# Display.net
KiCad netlist of a schematic drawn in Altium Designer
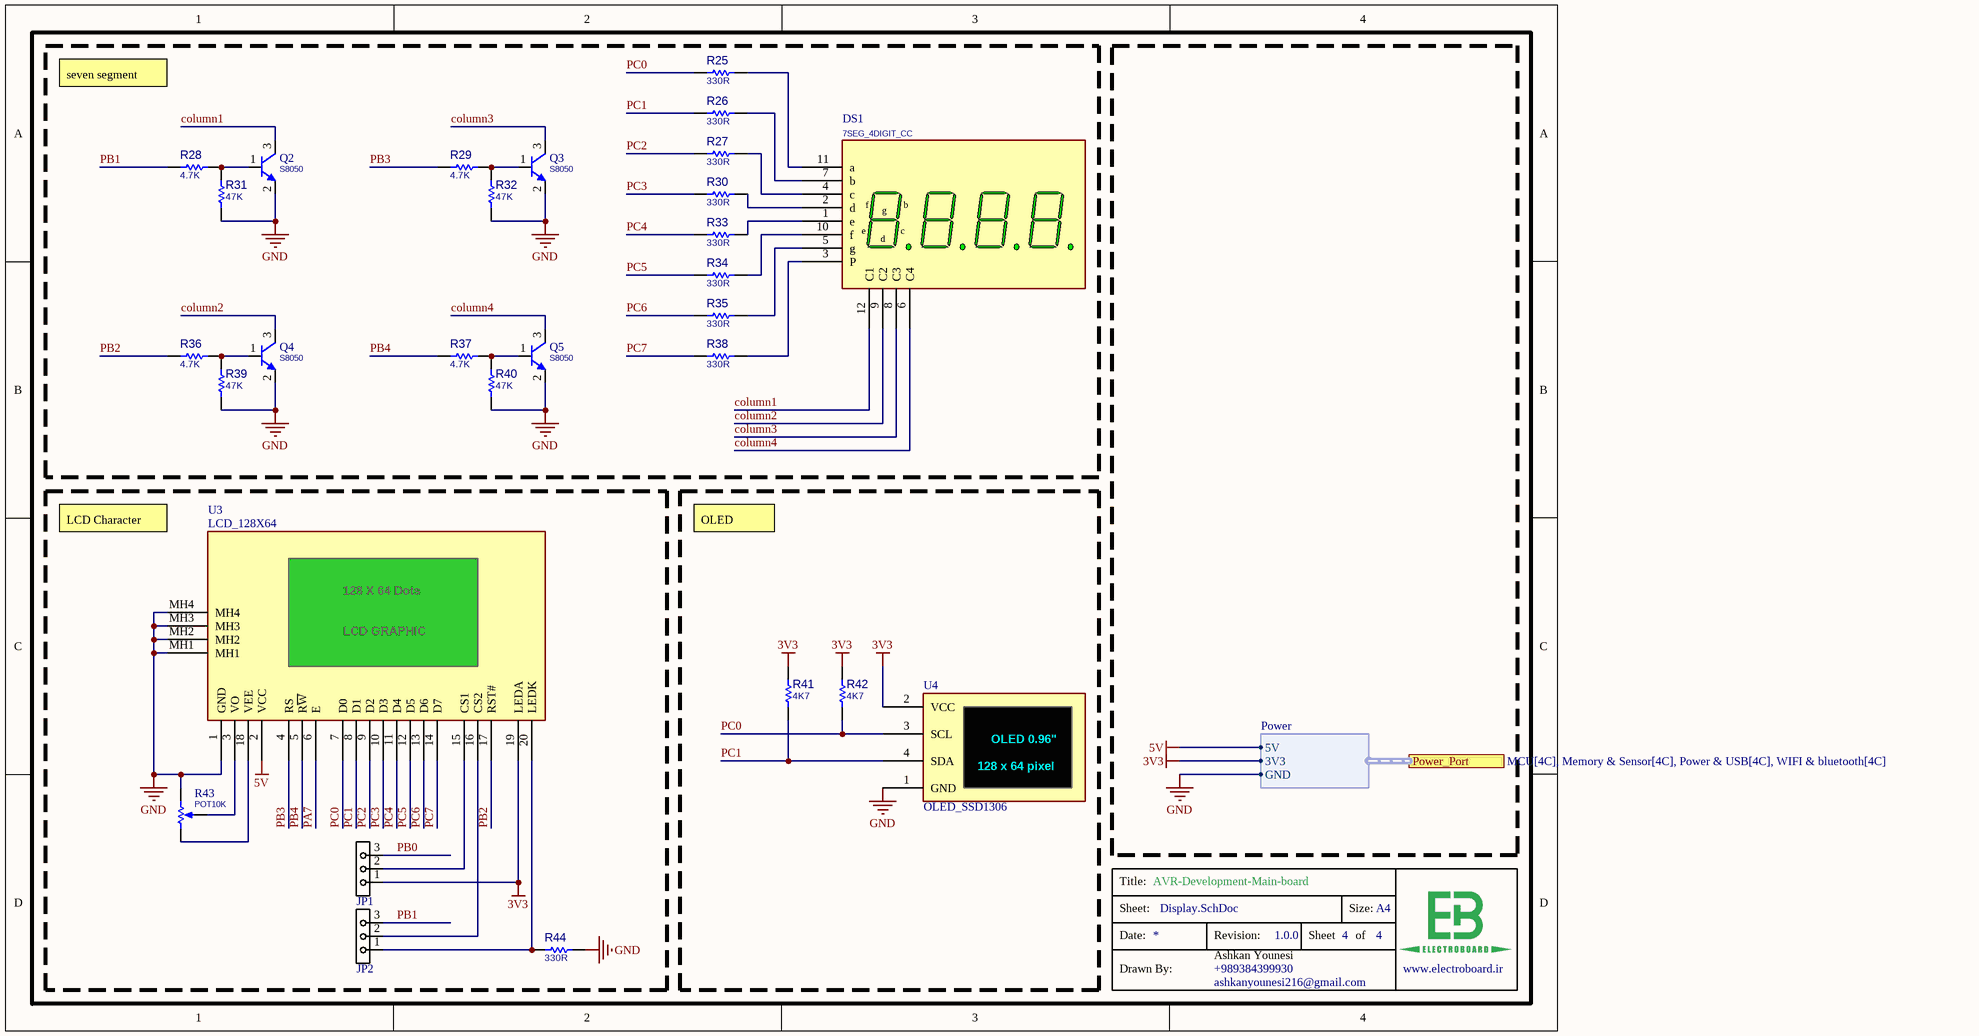
[diagram p0: Display.SchDoc]

(export (version "E")
  (design (tool "Eeschema 10.0.6"))
  (components
    (comp (ref "DS1")
      (value "7SEG_4DIGIT_CC")
      (footprint "7SEGX4_12")
      (description "7SEGMENT, 4DIGIT, common cathode 5641")
      (fields (field (name "MANF_P#") "DPY-4CK"))
      (libsource (lib "7seg(LED)") (part "7SEG_4DIGIT_CC"))
    )
    (comp (ref "JP1")
      (value "JMPHDR3PIN")
      (footprint "JP_3")
      (description "JUMPER, HEADER 3PIN")
      (fields (field (name "MANF") "MANF") (field (name "MANF_P#") "MANF_P#"))
      (libsource (lib "test-tp_jumper") (part "JUMPER_HDR_3P"))
    )
    (comp (ref "JP2")
      (value "JMPHDR3PIN")
      (footprint "JP_3")
      (description "JUMPER, HEADER 3PIN")
      (fields (field (name "MANF") "MANF") (field (name "MANF_P#") "MANF_P#"))
      (libsource (lib "test-tp_jumper") (part "JUMPER_HDR_3P"))
    )
    (comp (ref "Q2")
      (value "S8050")
      (footprint "SOT23_3")
      (description "BJT, NPN, 25v, 0.5A, SMD, SOT23")
      (libsource (lib "transistor_bjt") (part "NPN_S8050_SOT23"))
    )
    (comp (ref "Q3")
      (value "S8050")
      (footprint "SOT23_3")
      (description "BJT, NPN, 25v, 0.5A, SMD, SOT23")
      (libsource (lib "transistor_bjt") (part "NPN_S8050_SOT23"))
    )
    (comp (ref "Q4")
      (value "S8050")
      (footprint "SOT23_3")
      (description "BJT, NPN, 25v, 0.5A, SMD, SOT23")
      (libsource (lib "transistor_bjt") (part "NPN_S8050_SOT23"))
    )
    (comp (ref "Q5")
      (value "S8050")
      (footprint "SOT23_3")
      (description "BJT, NPN, 25v, 0.5A, SMD, SOT23")
      (libsource (lib "transistor_bjt") (part "NPN_S8050_SOT23"))
    )
    (comp (ref "R25")
      (value "330R")
      (footprint "R0805")
      (description "RESISTOR, SMD")
      (libsource (lib "passive_smd") (part "RES_SMD_0805"))
    )
    (comp (ref "R26")
      (value "330R")
      (footprint "R0805")
      (description "RESISTOR, SMD")
      (libsource (lib "passive_smd") (part "RES_SMD_0805"))
    )
    (comp (ref "R27")
      (value "330R")
      (footprint "R0805")
      (description "RESISTOR, SMD")
      (libsource (lib "passive_smd") (part "RES_SMD_0805"))
    )
    (comp (ref "R28")
      (value "4.7K")
      (footprint "R0805")
      (description "RESISTOR, SMD")
      (libsource (lib "passive_smd") (part "RES_SMD_0805"))
    )
    (comp (ref "R29")
      (value "4.7K")
      (footprint "R0805")
      (description "RESISTOR, SMD")
      (libsource (lib "passive_smd") (part "RES_SMD_0805"))
    )
    (comp (ref "R30")
      (value "330R")
      (footprint "R0805")
      (description "RESISTOR, SMD")
      (libsource (lib "passive_smd") (part "RES_SMD_0805"))
    )
    (comp (ref "R31")
      (value "47K")
      (footprint "R0805")
      (description "RESISTOR, SMD")
      (libsource (lib "passive_smd") (part "RES_SMD_0805"))
    )
    (comp (ref "R32")
      (value "47K")
      (footprint "R0805")
      (description "RESISTOR, SMD")
      (libsource (lib "passive_smd") (part "RES_SMD_0805"))
    )
    (comp (ref "R33")
      (value "330R")
      (footprint "R0805")
      (description "RESISTOR, SMD")
      (libsource (lib "passive_smd") (part "RES_SMD_0805"))
    )
    (comp (ref "R34")
      (value "330R")
      (footprint "R0805")
      (description "RESISTOR, SMD")
      (libsource (lib "passive_smd") (part "RES_SMD_0805"))
    )
    (comp (ref "R35")
      (value "330R")
      (footprint "R0805")
      (description "RESISTOR, SMD")
      (libsource (lib "passive_smd") (part "RES_SMD_0805"))
    )
    (comp (ref "R36")
      (value "4.7K")
      (footprint "R0805")
      (description "RESISTOR, SMD")
      (libsource (lib "passive_smd") (part "RES_SMD_0805"))
    )
    (comp (ref "R37")
      (value "4.7K")
      (footprint "R0805")
      (description "RESISTOR, SMD")
      (libsource (lib "passive_smd") (part "RES_SMD_0805"))
    )
    (comp (ref "R38")
      (value "330R")
      (footprint "R0805")
      (description "RESISTOR, SMD")
      (libsource (lib "passive_smd") (part "RES_SMD_0805"))
    )
    (comp (ref "R39")
      (value "47K")
      (footprint "R0805")
      (description "RESISTOR, SMD")
      (libsource (lib "passive_smd") (part "RES_SMD_0805"))
    )
    (comp (ref "R40")
      (value "47K")
      (footprint "R0805")
      (description "RESISTOR, SMD")
      (libsource (lib "passive_smd") (part "RES_SMD_0805"))
    )
    (comp (ref "R41")
      (value "4K7")
      (footprint "R0805")
      (description "RESISTOR, SMD")
      (libsource (lib "passive_smd") (part "RES_SMD_0805"))
    )
    (comp (ref "R42")
      (value "4K7")
      (footprint "R0805")
      (description "RESISTOR, SMD")
      (libsource (lib "passive_smd") (part "RES_SMD_0805"))
    )
    (comp (ref "R43")
      (value "POT10K")
      (footprint "POT_3296W")
      (description "RESISTOR, THD, Potentiometer Multiturn, most Popular")
      (libsource (lib "resistor_pot_trimmer") (part "RES_THD_POT_MULTITURN"))
    )
    (comp (ref "R44")
      (value "330R")
      (footprint "R0805")
      (description "RESISTOR, SMD")
      (libsource (lib "passive_smd") (part "RES_SMD_0805"))
    )
    (comp (ref "U3")
      (value "LCD_128X64")
      (footprint "LCDG_128X64_GRN")
      (description "LCD Graphic Disp, 128X64, with KS108 Controller")
      (fields (field (name "MANF") "Winstar") (field (name "MANF_P#") "TS12864A-2, WG12864A-1"))
      (libsource (lib "lcd") (part "LCDG_128X64_GRN"))
    )
    (comp (ref "U4")
      (value "OLED_SSD1306")
      (footprint "OLED_SSD1306_64_I2C")
      (description "OLED, SSD1306, 0.96\", 128X64, BREAKOUT I2C")
      (fields (field (name "MANF_P#") "OLED_SSD1306_I2C"))
      (libsource (lib "oled") (part "OLED_SSD1306_64_I2C"))
    )
  )
  (nets
    (net (code "2") (name "/PA7") (class "Default")
      (node (ref "U3") (pin "6") (pinfunction "E_6") (pintype "passive"))
    )
    (net (code "3") (name "/PB0") (class "Default")
      (node (ref "JP1") (pin "3") (pinfunction "3_3") (pintype "passive"))
    )
    (net (code "4") (name "/PB1") (class "Default")
      (node (ref "JP2") (pin "3") (pinfunction "3_3") (pintype "passive"))
      (node (ref "R28") (pin "1") (pinfunction "1_1") (pintype "passive"))
    )
    (net (code "5") (name "/PB2") (class "Default")
      (node (ref "R36") (pin "1") (pinfunction "1_1") (pintype "passive"))
      (node (ref "U3") (pin "17") (pinfunction "RST#_17") (pintype "passive"))
    )
    (net (code "6") (name "/PB3") (class "Default")
      (node (ref "R29") (pin "1") (pinfunction "1_1") (pintype "passive"))
      (node (ref "U3") (pin "4") (pinfunction "RS_4") (pintype "passive"))
    )
    (net (code "7") (name "/PB4") (class "Default")
      (node (ref "R37") (pin "1") (pinfunction "1_1") (pintype "passive"))
      (node (ref "U3") (pin "5") (pinfunction "R~{W}_5") (pintype "passive"))
    )
    (net (code "8") (name "/PC0") (class "Default")
      (node (ref "R25") (pin "1") (pinfunction "1_1") (pintype "passive"))
      (node (ref "R42") (pin "2") (pinfunction "2_2") (pintype "passive"))
      (node (ref "U3") (pin "7") (pinfunction "D0_7") (pintype "passive"))
      (node (ref "U4") (pin "3") (pinfunction "SCL_3") (pintype "passive"))
    )
    (net (code "9") (name "/PC1") (class "Default")
      (node (ref "R26") (pin "1") (pinfunction "1_1") (pintype "passive"))
      (node (ref "R41") (pin "2") (pinfunction "2_2") (pintype "passive"))
      (node (ref "U3") (pin "8") (pinfunction "D1_8") (pintype "passive"))
      (node (ref "U4") (pin "4") (pinfunction "SDA_4") (pintype "passive"))
    )
    (net (code "10") (name "/PC2") (class "Default")
      (node (ref "R27") (pin "1") (pinfunction "1_1") (pintype "passive"))
      (node (ref "U3") (pin "9") (pinfunction "D2_9") (pintype "passive"))
    )
    (net (code "11") (name "/PC3") (class "Default")
      (node (ref "R30") (pin "1") (pinfunction "1_1") (pintype "passive"))
      (node (ref "U3") (pin "10") (pinfunction "D3_10") (pintype "passive"))
    )
    (net (code "12") (name "/PC4") (class "Default")
      (node (ref "R33") (pin "1") (pinfunction "1_1") (pintype "passive"))
      (node (ref "U3") (pin "11") (pinfunction "D4_11") (pintype "passive"))
    )
    (net (code "13") (name "/PC5") (class "Default")
      (node (ref "R34") (pin "1") (pinfunction "1_1") (pintype "passive"))
      (node (ref "U3") (pin "12") (pinfunction "D5_12") (pintype "passive"))
    )
    (net (code "14") (name "/PC6") (class "Default")
      (node (ref "R35") (pin "1") (pinfunction "1_1") (pintype "passive"))
      (node (ref "U3") (pin "13") (pinfunction "D6_13") (pintype "passive"))
    )
    (net (code "15") (name "/PC7") (class "Default")
      (node (ref "R38") (pin "1") (pinfunction "1_1") (pintype "passive"))
      (node (ref "U3") (pin "14") (pinfunction "D7_14") (pintype "passive"))
    )
    (net (code "16") (name "/column1") (class "Default")
      (node (ref "DS1") (pin "12") (pinfunction "C1_12") (pintype "passive"))
      (node (ref "Q2") (pin "3") (pinfunction "C_3") (pintype "passive"))
    )
    (net (code "17") (name "/column2") (class "Default")
      (node (ref "DS1") (pin "9") (pinfunction "C2_9") (pintype "passive"))
      (node (ref "Q4") (pin "3") (pinfunction "C_3") (pintype "passive"))
    )
    (net (code "18") (name "/column3") (class "Default")
      (node (ref "DS1") (pin "8") (pinfunction "C3_8") (pintype "passive"))
      (node (ref "Q3") (pin "3") (pinfunction "C_3") (pintype "passive"))
    )
    (net (code "19") (name "/column4") (class "Default")
      (node (ref "DS1") (pin "6") (pinfunction "C4_6") (pintype "passive"))
      (node (ref "Q5") (pin "3") (pinfunction "C_3") (pintype "passive"))
    )
    (net (code "21") (name "3V3") (class "Default")
      (node (ref "JP1") (pin "1") (pinfunction "1_1") (pintype "passive"))
      (node (ref "R41") (pin "1") (pinfunction "1_1") (pintype "passive"))
      (node (ref "R42") (pin "1") (pinfunction "1_1") (pintype "passive"))
      (node (ref "U3") (pin "19") (pinfunction "LEDA_19") (pintype "passive"))
      (node (ref "U4") (pin "2") (pinfunction "VCC_2") (pintype "passive"))
    )
    (net (code "22") (name "5V") (class "Default")
      (node (ref "U3") (pin "2") (pinfunction "VCC_2") (pintype "passive"))
    )
    (net (code "23") (name "GND") (class "Default")
      (node (ref "Q2") (pin "2") (pinfunction "E_2") (pintype "passive"))
      (node (ref "Q3") (pin "2") (pinfunction "E_2") (pintype "passive"))
      (node (ref "Q4") (pin "2") (pinfunction "E_2") (pintype "passive"))
      (node (ref "Q5") (pin "2") (pinfunction "E_2") (pintype "passive"))
      (node (ref "R31") (pin "1") (pinfunction "1_1") (pintype "passive"))
      (node (ref "R32") (pin "1") (pinfunction "1_1") (pintype "passive"))
      (node (ref "R39") (pin "1") (pinfunction "1_1") (pintype "passive"))
      (node (ref "R40") (pin "1") (pinfunction "1_1") (pintype "passive"))
      (node (ref "R43") (pin "3") (pinfunction "BOT_3") (pintype "passive"))
      (node (ref "R44") (pin "1") (pinfunction "1_1") (pintype "passive"))
      (node (ref "U3") (pin "1") (pinfunction "GND_1") (pintype "passive"))
      (node (ref "U3") (pin "MH1") (pinfunction "MH1_MH1") (pintype "passive"))
      (node (ref "U3") (pin "MH2") (pinfunction "MH2_MH2") (pintype "passive"))
      (node (ref "U3") (pin "MH3") (pinfunction "MH3_MH3") (pintype "passive"))
      (node (ref "U3") (pin "MH4") (pinfunction "MH4_MH4") (pintype "passive"))
      (node (ref "U4") (pin "1") (pinfunction "GND_1") (pintype "passive"))
    )
    (net (code "24") (name "Net-(DS1-P)") (class "Default")
      (node (ref "DS1") (pin "3") (pinfunction "P_3") (pintype "passive"))
      (node (ref "R38") (pin "2") (pinfunction "2_2") (pintype "passive"))
    )
    (net (code "25") (name "Net-(DS1-a)") (class "Default")
      (node (ref "DS1") (pin "11") (pinfunction "a_11") (pintype "passive"))
      (node (ref "R25") (pin "2") (pinfunction "2_2") (pintype "passive"))
    )
    (net (code "26") (name "Net-(DS1-b)") (class "Default")
      (node (ref "DS1") (pin "7") (pinfunction "b_7") (pintype "passive"))
      (node (ref "R26") (pin "2") (pinfunction "2_2") (pintype "passive"))
    )
    (net (code "27") (name "Net-(DS1-c)") (class "Default")
      (node (ref "DS1") (pin "4") (pinfunction "c_4") (pintype "passive"))
      (node (ref "R27") (pin "2") (pinfunction "2_2") (pintype "passive"))
    )
    (net (code "28") (name "Net-(DS1-d)") (class "Default")
      (node (ref "DS1") (pin "2") (pinfunction "d_2") (pintype "passive"))
      (node (ref "R30") (pin "2") (pinfunction "2_2") (pintype "passive"))
    )
    (net (code "29") (name "Net-(DS1-e)") (class "Default")
      (node (ref "DS1") (pin "1") (pinfunction "e_1") (pintype "passive"))
      (node (ref "R33") (pin "2") (pinfunction "2_2") (pintype "passive"))
    )
    (net (code "30") (name "Net-(DS1-f)") (class "Default")
      (node (ref "DS1") (pin "10") (pinfunction "f_10") (pintype "passive"))
      (node (ref "R34") (pin "2") (pinfunction "2_2") (pintype "passive"))
    )
    (net (code "31") (name "Net-(DS1-g)") (class "Default")
      (node (ref "DS1") (pin "5") (pinfunction "g_5") (pintype "passive"))
      (node (ref "R35") (pin "2") (pinfunction "2_2") (pintype "passive"))
    )
    (net (code "32") (name "Net-(Q2-B)") (class "Default")
      (node (ref "Q2") (pin "1") (pinfunction "B_1") (pintype "passive"))
      (node (ref "R28") (pin "2") (pinfunction "2_2") (pintype "passive"))
      (node (ref "R31") (pin "2") (pinfunction "2_2") (pintype "passive"))
    )
    (net (code "33") (name "Net-(Q3-B)") (class "Default")
      (node (ref "Q3") (pin "1") (pinfunction "B_1") (pintype "passive"))
      (node (ref "R29") (pin "2") (pinfunction "2_2") (pintype "passive"))
      (node (ref "R32") (pin "2") (pinfunction "2_2") (pintype "passive"))
    )
    (net (code "34") (name "Net-(Q4-B)") (class "Default")
      (node (ref "Q4") (pin "1") (pinfunction "B_1") (pintype "passive"))
      (node (ref "R36") (pin "2") (pinfunction "2_2") (pintype "passive"))
      (node (ref "R39") (pin "2") (pinfunction "2_2") (pintype "passive"))
    )
    (net (code "35") (name "Net-(Q5-B)") (class "Default")
      (node (ref "Q5") (pin "1") (pinfunction "B_1") (pintype "passive"))
      (node (ref "R37") (pin "2") (pinfunction "2_2") (pintype "passive"))
      (node (ref "R40") (pin "2") (pinfunction "2_2") (pintype "passive"))
    )
    (net (code "36") (name "Net-(R43-TAP)") (class "Default")
      (node (ref "R43") (pin "2") (pinfunction "TAP_2") (pintype "passive"))
      (node (ref "U3") (pin "3") (pinfunction "VO_3") (pintype "passive"))
    )
    (net (code "37") (name "Net-(R43-TOP)") (class "Default")
      (node (ref "R43") (pin "1") (pinfunction "TOP_1") (pintype "passive"))
      (node (ref "U3") (pin "18") (pinfunction "VEE_18") (pintype "passive"))
    )
    (net (code "38") (name "Net-(U3-CS1)") (class "Default")
      (node (ref "JP1") (pin "2") (pinfunction "2_2") (pintype "passive"))
      (node (ref "U3") (pin "15") (pinfunction "CS1_15") (pintype "passive"))
    )
    (net (code "39") (name "Net-(U3-CS2)") (class "Default")
      (node (ref "JP2") (pin "2") (pinfunction "2_2") (pintype "passive"))
      (node (ref "U3") (pin "16") (pinfunction "CS2_16") (pintype "passive"))
    )
    (net (code "40") (name "Net-(U3-LEDK)") (class "Default")
      (node (ref "JP2") (pin "1") (pinfunction "1_1") (pintype "passive"))
      (node (ref "R44") (pin "2") (pinfunction "2_2") (pintype "passive"))
      (node (ref "U3") (pin "20") (pinfunction "LEDK_20") (pintype "passive"))
    )
  )
)
